# PWMExpansion.net
KiCad netlist of a schematic drawn in EAGLE
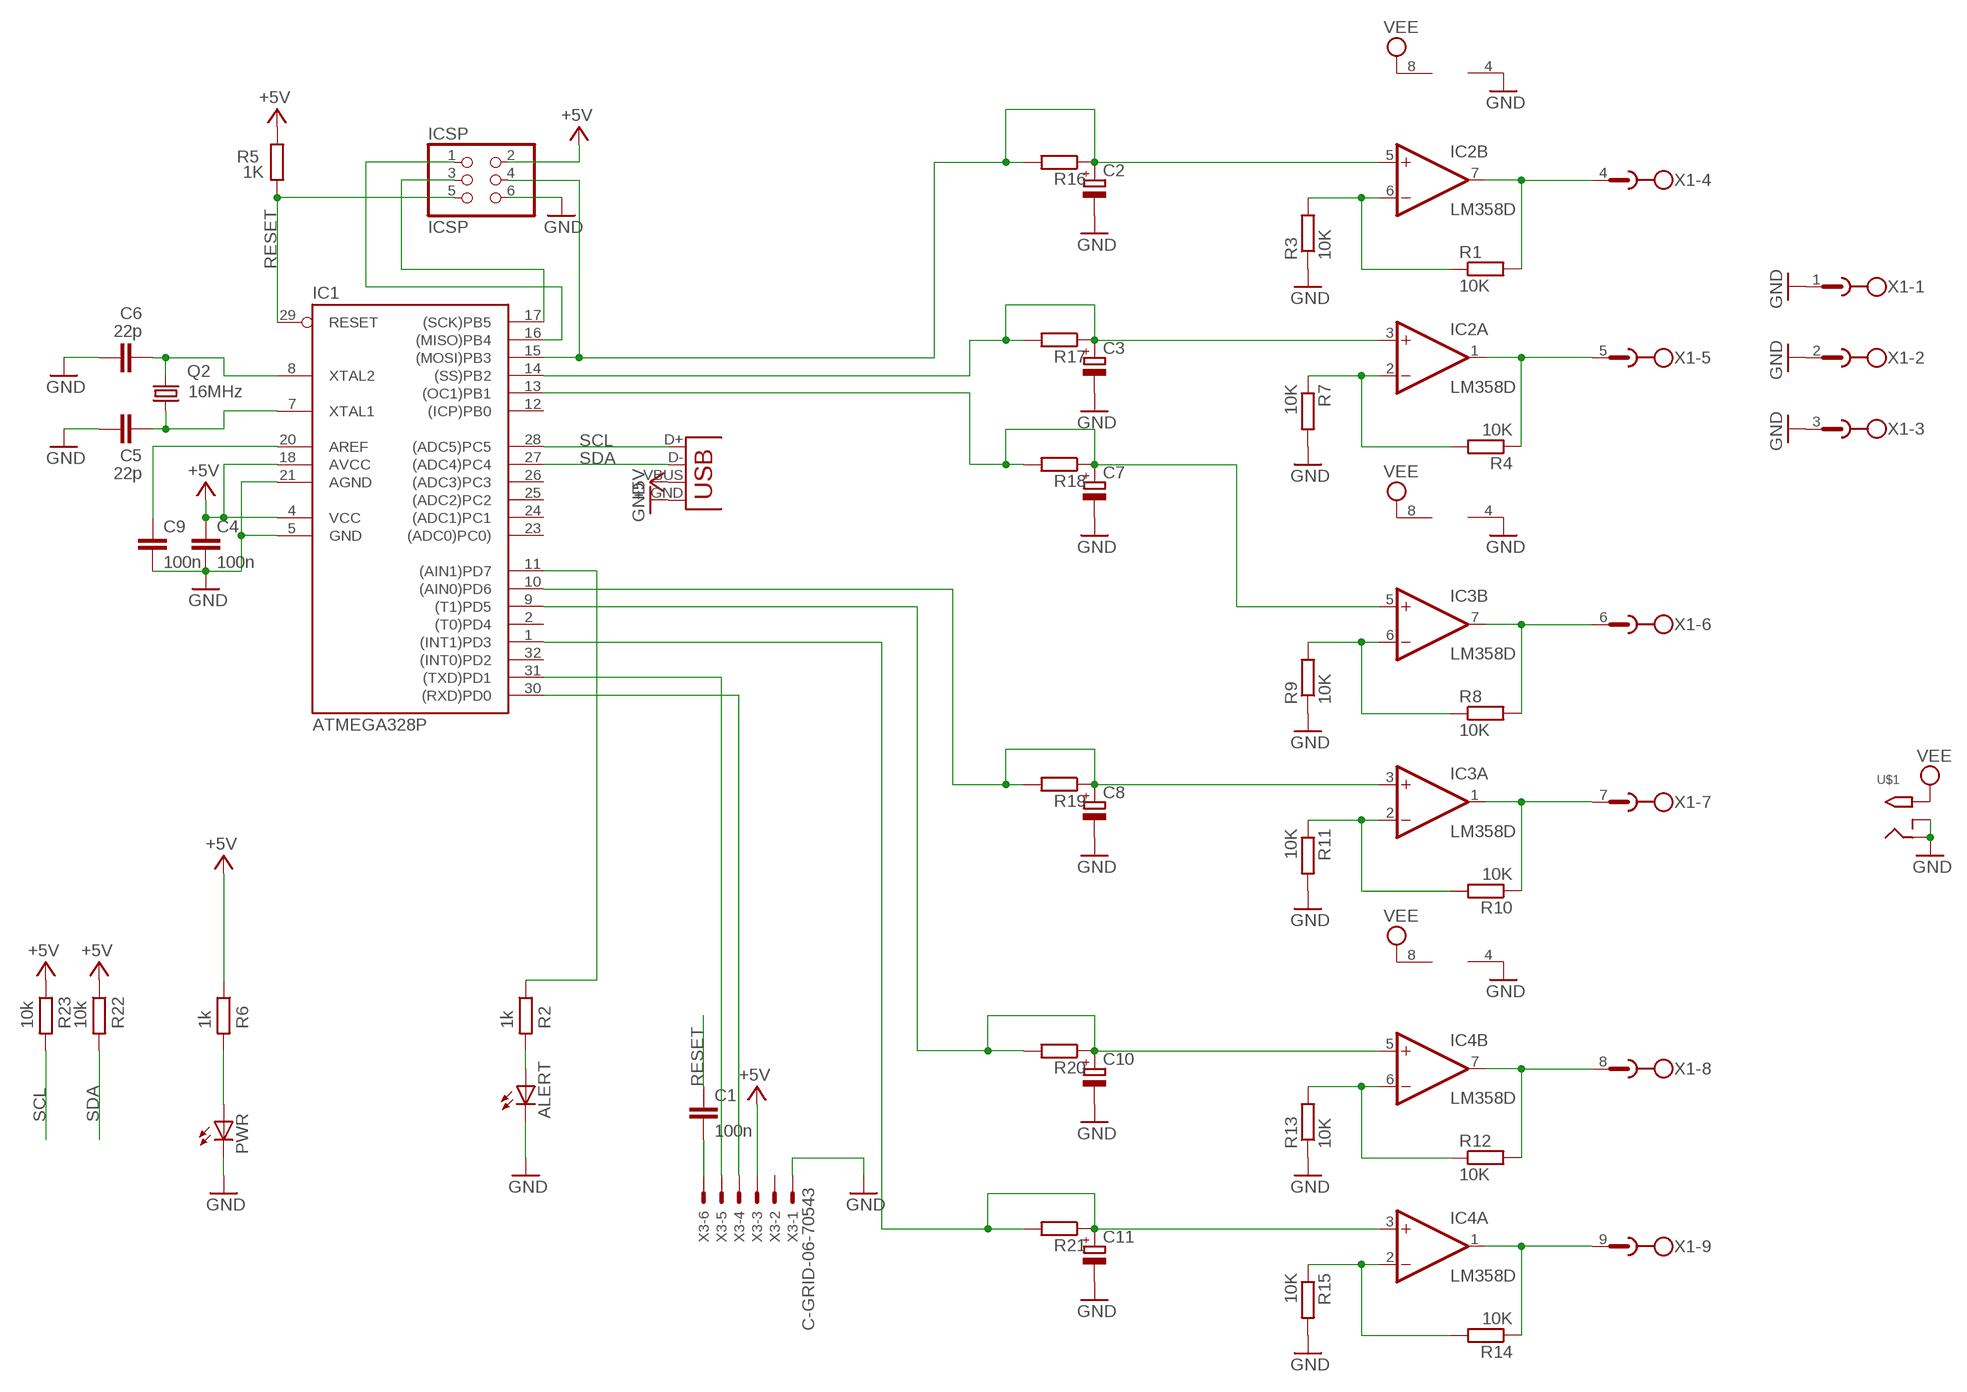
[diagram p0: schematic, sheet 1]

(export (version "E")
  (design (tool "Eeschema 10.0.6"))
  (components
    (comp (ref "ALERT")
      (value "LED3MM")
      (footprint "eagle-import:LED3MM")
      (libsource (lib "eagle-import") (part "LED3MM"))
    )
    (comp (ref "C1")
      (value "100n")
      (footprint "eagle-import:C0805")
      (libsource (lib "eagle-import") (part "C-EUC0805"))
    )
    (comp (ref "C2")
      (value "CPOL-EUA/3216-18W")
      (footprint "eagle-import:A_3216-18W")
      (libsource (lib "eagle-import") (part "CPOL-EUA/3216-18W"))
    )
    (comp (ref "C3")
      (value "CPOL-EUA/3216-18W")
      (footprint "eagle-import:A_3216-18W")
      (libsource (lib "eagle-import") (part "CPOL-EUA/3216-18W"))
    )
    (comp (ref "C4")
      (value "100n")
      (footprint "eagle-import:C0805")
      (libsource (lib "eagle-import") (part "C-EUC0805"))
    )
    (comp (ref "C5")
      (value "22p")
      (footprint "eagle-import:C0805")
      (libsource (lib "eagle-import") (part "C-EUC0805"))
    )
    (comp (ref "C6")
      (value "22p")
      (footprint "eagle-import:C0805")
      (libsource (lib "eagle-import") (part "C-EUC0805"))
    )
    (comp (ref "C7")
      (value "CPOL-EUA/3216-18W")
      (footprint "eagle-import:A_3216-18W")
      (libsource (lib "eagle-import") (part "CPOL-EUA/3216-18W"))
    )
    (comp (ref "C8")
      (value "CPOL-EUA/3216-18W")
      (footprint "eagle-import:A_3216-18W")
      (libsource (lib "eagle-import") (part "CPOL-EUA/3216-18W"))
    )
    (comp (ref "C9")
      (value "100n")
      (footprint "eagle-import:C0805")
      (libsource (lib "eagle-import") (part "C-EUC0805"))
    )
    (comp (ref "C10")
      (value "CPOL-EUA/3216-18W")
      (footprint "eagle-import:A_3216-18W")
      (libsource (lib "eagle-import") (part "CPOL-EUA/3216-18W"))
    )
    (comp (ref "C11")
      (value "CPOL-EUA/3216-18W")
      (footprint "eagle-import:A_3216-18W")
      (libsource (lib "eagle-import") (part "CPOL-EUA/3216-18W"))
    )
    (comp (ref "IC1")
      (value "ATMEGA328P")
      (footprint "eagle-import:TQFP32-08")
      (libsource (lib "eagle-import") (part "AT90S4433A"))
    )
    (comp (ref "IC2")
      (value "LM358D")
      (footprint "eagle-import:SO08")
      (libsource (lib "eagle-import") (part "LM358D"))
    )
    (comp (ref "IC3")
      (value "LM358D")
      (footprint "eagle-import:SO08")
      (libsource (lib "eagle-import") (part "LM358D"))
    )
    (comp (ref "IC4")
      (value "LM358D")
      (footprint "eagle-import:SO08")
      (libsource (lib "eagle-import") (part "LM358D"))
    )
    (comp (ref "ICSP")
      (value "ICSP")
      (footprint "eagle-import:2X03")
      (libsource (lib "eagle-import") (part "PINHD-2X3"))
    )
    (comp (ref "PWR")
      (value "LED3MM")
      (footprint "eagle-import:LED3MM")
      (libsource (lib "eagle-import") (part "LED3MM"))
    )
    (comp (ref "Q2")
      (value "16MHz")
      (footprint "eagle-import:HC49_S")
      (libsource (lib "eagle-import") (part "CRYTALHC49S"))
    )
    (comp (ref "R1")
      (value "10K")
      (footprint "eagle-import:R0805")
      (libsource (lib "eagle-import") (part "R-EU_R0805"))
    )
    (comp (ref "R2")
      (value "1k")
      (footprint "eagle-import:R0805")
      (libsource (lib "eagle-import") (part "R-EU_R0805"))
    )
    (comp (ref "R3")
      (value "10K")
      (footprint "eagle-import:R0805")
      (libsource (lib "eagle-import") (part "R-EU_R0805"))
    )
    (comp (ref "R4")
      (value "10K")
      (footprint "eagle-import:R0805")
      (libsource (lib "eagle-import") (part "R-EU_R0805"))
    )
    (comp (ref "R5")
      (value "1K")
      (footprint "eagle-import:R0805")
      (libsource (lib "eagle-import") (part "R-EU_R0805"))
    )
    (comp (ref "R6")
      (value "1k")
      (footprint "eagle-import:R0805")
      (libsource (lib "eagle-import") (part "R-EU_R0805"))
    )
    (comp (ref "R7")
      (value "10K")
      (footprint "eagle-import:R0805")
      (libsource (lib "eagle-import") (part "R-EU_R0805"))
    )
    (comp (ref "R8")
      (value "10K")
      (footprint "eagle-import:R0805")
      (libsource (lib "eagle-import") (part "R-EU_R0805"))
    )
    (comp (ref "R9")
      (value "10K")
      (footprint "eagle-import:R0805")
      (libsource (lib "eagle-import") (part "R-EU_R0805"))
    )
    (comp (ref "R10")
      (value "10K")
      (footprint "eagle-import:R0805")
      (libsource (lib "eagle-import") (part "R-EU_R0805"))
    )
    (comp (ref "R11")
      (value "10K")
      (footprint "eagle-import:R0805")
      (libsource (lib "eagle-import") (part "R-EU_R0805"))
    )
    (comp (ref "R12")
      (value "10K")
      (footprint "eagle-import:R0805")
      (libsource (lib "eagle-import") (part "R-EU_R0805"))
    )
    (comp (ref "R13")
      (value "10K")
      (footprint "eagle-import:R0805")
      (libsource (lib "eagle-import") (part "R-EU_R0805"))
    )
    (comp (ref "R14")
      (value "10K")
      (footprint "eagle-import:R0805")
      (libsource (lib "eagle-import") (part "R-EU_R0805"))
    )
    (comp (ref "R15")
      (value "10K")
      (footprint "eagle-import:R0805")
      (libsource (lib "eagle-import") (part "R-EU_R0805"))
    )
    (comp (ref "R16")
      (value "R-EU_R0805")
      (footprint "eagle-import:R0805")
      (libsource (lib "eagle-import") (part "R-EU_R0805"))
    )
    (comp (ref "R17")
      (value "R-EU_R0805")
      (footprint "eagle-import:R0805")
      (libsource (lib "eagle-import") (part "R-EU_R0805"))
    )
    (comp (ref "R18")
      (value "R-EU_R0805")
      (footprint "eagle-import:R0805")
      (libsource (lib "eagle-import") (part "R-EU_R0805"))
    )
    (comp (ref "R19")
      (value "R-EU_R0805")
      (footprint "eagle-import:R0805")
      (libsource (lib "eagle-import") (part "R-EU_R0805"))
    )
    (comp (ref "R20")
      (value "R-EU_R0805")
      (footprint "eagle-import:R0805")
      (libsource (lib "eagle-import") (part "R-EU_R0805"))
    )
    (comp (ref "R21")
      (value "R-EU_R0805")
      (footprint "eagle-import:R0805")
      (libsource (lib "eagle-import") (part "R-EU_R0805"))
    )
    (comp (ref "R22")
      (value "10k")
      (footprint "eagle-import:R0805")
      (libsource (lib "eagle-import") (part "R-EU_R0805"))
    )
    (comp (ref "R23")
      (value "10k")
      (footprint "eagle-import:R0805")
      (libsource (lib "eagle-import") (part "R-EU_R0805"))
    )
    (comp (ref "U$1")
      (value "2.1MMJACKTHM")
      (footprint "eagle-import:PJ-102A")
      (libsource (lib "eagle-import") (part "2.1MMJACKTHM"))
    )
    (comp (ref "X1")
      (value "MSTBV9")
      (footprint "eagle-import:MSTBV9")
      (libsource (lib "eagle-import") (part "MSTBV9"))
    )
    (comp (ref "X3")
      (value "C-GRID-06-70543")
      (footprint "eagle-import:70543-06")
      (libsource (lib "eagle-import") (part "C-GRID-06-70543"))
    )
    (comp (ref "X5")
      (value "USBSMD")
      (footprint "eagle-import:USB-MINIB")
      (libsource (lib "eagle-import") (part "USBSMD"))
    )
  )
  (nets
    (net (code "1") (name "+5V") (class "Default")
      (node (ref "C4") (pin "1") (pinfunction "1_1") (pintype "passive"))
      (node (ref "IC1") (pin "18") (pinfunction "AVCC_18") (pintype "power_in"))
      (node (ref "IC1") (pin "4") (pinfunction "VCC_4") (pintype "power_in"))
      (node (ref "ICSP") (pin "2") (pinfunction "2_2") (pintype "passive"))
      (node (ref "R22") (pin "1") (pinfunction "1_1") (pintype "passive"))
      (node (ref "R23") (pin "1") (pinfunction "1_1") (pintype "passive"))
      (node (ref "R5") (pin "2") (pinfunction "2_2") (pintype "passive"))
      (node (ref "R6") (pin "1") (pinfunction "1_1") (pintype "passive"))
      (node (ref "X3") (pin "3") (pinfunction "S_3") (pintype "passive"))
      (node (ref "X5") (pin "VBUS") (pinfunction "VBUS_VBUS") (pintype "bidirectional"))
    )
    (net (code "2") (name "/RESET") (class "Default")
      (node (ref "C1") (pin "1") (pinfunction "1_1") (pintype "passive"))
      (node (ref "IC1") (pin "29") (pinfunction "RESET_29") (pintype "input"))
      (node (ref "ICSP") (pin "5") (pinfunction "5_5") (pintype "passive"))
      (node (ref "R5") (pin "1") (pinfunction "1_1") (pintype "passive"))
    )
    (net (code "3") (name "/SCL") (class "Default")
      (node (ref "IC1") (pin "28") (pinfunction "(ADC5)PC5_28") (pintype "bidirectional"))
      (node (ref "R23") (pin "2") (pinfunction "2_2") (pintype "passive"))
      (node (ref "X5") (pin "D+") (pinfunction "D+_D+") (pintype "bidirectional"))
    )
    (net (code "4") (name "/SDA") (class "Default")
      (node (ref "IC1") (pin "27") (pinfunction "(ADC4)PC4_27") (pintype "bidirectional"))
      (node (ref "R22") (pin "2") (pinfunction "2_2") (pintype "passive"))
      (node (ref "X5") (pin "D-") (pinfunction "D-_D-") (pintype "bidirectional"))
    )
    (net (code "5") (name "GND") (class "Default")
      (node (ref "ALERT") (pin "K") (pinfunction "C_K") (pintype "passive"))
      (node (ref "C10") (pin "-") (pinfunction "-_-") (pintype "passive"))
      (node (ref "C11") (pin "-") (pinfunction "-_-") (pintype "passive"))
      (node (ref "C2") (pin "-") (pinfunction "-_-") (pintype "passive"))
      (node (ref "C3") (pin "-") (pinfunction "-_-") (pintype "passive"))
      (node (ref "C4") (pin "2") (pinfunction "2_2") (pintype "passive"))
      (node (ref "C5") (pin "1") (pinfunction "1_1") (pintype "passive"))
      (node (ref "C6") (pin "1") (pinfunction "1_1") (pintype "passive"))
      (node (ref "C7") (pin "-") (pinfunction "-_-") (pintype "passive"))
      (node (ref "C8") (pin "-") (pinfunction "-_-") (pintype "passive"))
      (node (ref "C9") (pin "2") (pinfunction "2_2") (pintype "passive"))
      (node (ref "IC1") (pin "21") (pinfunction "AGND_21") (pintype "power_in"))
      (node (ref "IC1") (pin "5") (pinfunction "GND_5") (pintype "power_in"))
      (node (ref "IC2") (pin "4") (pinfunction "V-_4") (pintype "power_in"))
      (node (ref "IC3") (pin "4") (pinfunction "V-_4") (pintype "power_in"))
      (node (ref "IC4") (pin "4") (pinfunction "V-_4") (pintype "power_in"))
      (node (ref "ICSP") (pin "6") (pinfunction "6_6") (pintype "passive"))
      (node (ref "PWR") (pin "K") (pinfunction "C_K") (pintype "passive"))
      (node (ref "R11") (pin "2") (pinfunction "2_2") (pintype "passive"))
      (node (ref "R13") (pin "1") (pinfunction "1_1") (pintype "passive"))
      (node (ref "R15") (pin "2") (pinfunction "2_2") (pintype "passive"))
      (node (ref "R3") (pin "1") (pinfunction "1_1") (pintype "passive"))
      (node (ref "R7") (pin "2") (pinfunction "2_2") (pintype "passive"))
      (node (ref "R9") (pin "1") (pinfunction "1_1") (pintype "passive"))
      (node (ref "U$1") (pin "RING") (pinfunction "RING_RING") (pintype "bidirectional"))
      (node (ref "U$1") (pin "RING_SW") (pinfunction "RING_SW_RING_SW") (pintype "bidirectional"))
      (node (ref "X1") (pin "1") (pinfunction "1_1") (pintype "passive"))
      (node (ref "X1") (pin "2") (pinfunction "1_2") (pintype "passive"))
      (node (ref "X1") (pin "3") (pinfunction "1_3") (pintype "passive"))
      (node (ref "X3") (pin "1") (pinfunction "S_1") (pintype "passive"))
      (node (ref "X5") (pin "GND") (pinfunction "GND_GND") (pintype "bidirectional"))
    )
    (net (code "6") (name "Net-(ALERT-PadA)") (class "Default")
      (node (ref "ALERT") (pin "A") (pinfunction "A_A") (pintype "passive"))
      (node (ref "R2") (pin "2") (pinfunction "2_2") (pintype "passive"))
    )
    (net (code "7") (name "Net-(IC1-(AIN0)PD6)") (class "Default")
      (node (ref "C8") (pin "+") (pinfunction "+_+") (pintype "passive"))
      (node (ref "IC1") (pin "10") (pinfunction "(AIN0)PD6_10") (pintype "bidirectional"))
      (node (ref "IC3") (pin "3") (pinfunction "+IN_3") (pintype "input"))
      (node (ref "R19") (pin "1") (pinfunction "1_1") (pintype "passive"))
      (node (ref "R19") (pin "2") (pinfunction "2_2") (pintype "passive"))
    )
    (net (code "8") (name "Net-(IC1-(AIN1)PD7)") (class "Default")
      (node (ref "IC1") (pin "11") (pinfunction "(AIN1)PD7_11") (pintype "bidirectional"))
      (node (ref "R2") (pin "1") (pinfunction "1_1") (pintype "passive"))
    )
    (net (code "9") (name "Net-(IC1-(INT1)PD3)") (class "Default")
      (node (ref "C11") (pin "+") (pinfunction "+_+") (pintype "passive"))
      (node (ref "IC1") (pin "1") (pinfunction "(INT1)PD3_1") (pintype "bidirectional"))
      (node (ref "IC4") (pin "3") (pinfunction "+IN_3") (pintype "input"))
      (node (ref "R21") (pin "1") (pinfunction "1_1") (pintype "passive"))
      (node (ref "R21") (pin "2") (pinfunction "2_2") (pintype "passive"))
    )
    (net (code "10") (name "Net-(IC1-(MISO)PB4)") (class "Default")
      (node (ref "IC1") (pin "16") (pinfunction "(MISO)PB4_16") (pintype "bidirectional"))
      (node (ref "ICSP") (pin "1") (pinfunction "1_1") (pintype "passive"))
    )
    (net (code "11") (name "Net-(IC1-(MOSI)PB3)") (class "Default")
      (node (ref "C2") (pin "+") (pinfunction "+_+") (pintype "passive"))
      (node (ref "IC1") (pin "15") (pinfunction "(MOSI)PB3_15") (pintype "bidirectional"))
      (node (ref "IC2") (pin "5") (pinfunction "+IN_5") (pintype "input"))
      (node (ref "ICSP") (pin "4") (pinfunction "4_4") (pintype "passive"))
      (node (ref "R16") (pin "1") (pinfunction "1_1") (pintype "passive"))
      (node (ref "R16") (pin "2") (pinfunction "2_2") (pintype "passive"))
    )
    (net (code "12") (name "Net-(IC1-(OC1)PB1)") (class "Default")
      (node (ref "C7") (pin "+") (pinfunction "+_+") (pintype "passive"))
      (node (ref "IC1") (pin "13") (pinfunction "(OC1)PB1_13") (pintype "bidirectional"))
      (node (ref "IC3") (pin "5") (pinfunction "+IN_5") (pintype "input"))
      (node (ref "R18") (pin "1") (pinfunction "1_1") (pintype "passive"))
      (node (ref "R18") (pin "2") (pinfunction "2_2") (pintype "passive"))
    )
    (net (code "13") (name "Net-(IC1-(RXD)PD0)") (class "Default")
      (node (ref "IC1") (pin "30") (pinfunction "(RXD)PD0_30") (pintype "bidirectional"))
      (node (ref "X3") (pin "4") (pinfunction "S_4") (pintype "passive"))
    )
    (net (code "14") (name "Net-(IC1-(SCK)PB5)") (class "Default")
      (node (ref "IC1") (pin "17") (pinfunction "(SCK)PB5_17") (pintype "bidirectional"))
      (node (ref "ICSP") (pin "3") (pinfunction "3_3") (pintype "passive"))
    )
    (net (code "15") (name "Net-(IC1-(SS)PB2)") (class "Default")
      (node (ref "C3") (pin "+") (pinfunction "+_+") (pintype "passive"))
      (node (ref "IC1") (pin "14") (pinfunction "(SS)PB2_14") (pintype "bidirectional"))
      (node (ref "IC2") (pin "3") (pinfunction "+IN_3") (pintype "input"))
      (node (ref "R17") (pin "1") (pinfunction "1_1") (pintype "passive"))
      (node (ref "R17") (pin "2") (pinfunction "2_2") (pintype "passive"))
    )
    (net (code "16") (name "Net-(IC1-(T1)PD5)") (class "Default")
      (node (ref "C10") (pin "+") (pinfunction "+_+") (pintype "passive"))
      (node (ref "IC1") (pin "9") (pinfunction "(T1)PD5_9") (pintype "bidirectional"))
      (node (ref "IC4") (pin "5") (pinfunction "+IN_5") (pintype "input"))
      (node (ref "R20") (pin "1") (pinfunction "1_1") (pintype "passive"))
      (node (ref "R20") (pin "2") (pinfunction "2_2") (pintype "passive"))
    )
    (net (code "17") (name "Net-(IC1-(TXD)PD1)") (class "Default")
      (node (ref "IC1") (pin "31") (pinfunction "(TXD)PD1_31") (pintype "bidirectional"))
      (node (ref "X3") (pin "5") (pinfunction "S_5") (pintype "passive"))
    )
    (net (code "18") (name "Net-(IC1-AREF)") (class "Default")
      (node (ref "C9") (pin "1") (pinfunction "1_1") (pintype "passive"))
      (node (ref "IC1") (pin "20") (pinfunction "AREF_20") (pintype "passive"))
    )
    (net (code "19") (name "Net-(IC1-XTAL1)") (class "Default")
      (node (ref "C5") (pin "2") (pinfunction "2_2") (pintype "passive"))
      (node (ref "IC1") (pin "7") (pinfunction "XTAL1_7") (pintype "bidirectional"))
      (node (ref "Q2") (pin "1") (pinfunction "1_1") (pintype "passive"))
    )
    (net (code "20") (name "Net-(IC1-XTAL2)") (class "Default")
      (node (ref "C6") (pin "2") (pinfunction "2_2") (pintype "passive"))
      (node (ref "IC1") (pin "8") (pinfunction "XTAL2_8") (pintype "bidirectional"))
      (node (ref "Q2") (pin "2") (pinfunction "2_2") (pintype "passive"))
    )
    (net (code "21") (name "Net-(IC2A--IN)") (class "Default")
      (node (ref "IC2") (pin "2") (pinfunction "-IN_2") (pintype "input"))
      (node (ref "R4") (pin "2") (pinfunction "2_2") (pintype "passive"))
      (node (ref "R7") (pin "1") (pinfunction "1_1") (pintype "passive"))
    )
    (net (code "22") (name "Net-(IC2A-OUT)") (class "Default")
      (node (ref "IC2") (pin "1") (pinfunction "OUT_1") (pintype "output"))
      (node (ref "R4") (pin "1") (pinfunction "1_1") (pintype "passive"))
      (node (ref "X1") (pin "5") (pinfunction "1_5") (pintype "passive"))
    )
    (net (code "23") (name "Net-(IC2B--IN)") (class "Default")
      (node (ref "IC2") (pin "6") (pinfunction "-IN_6") (pintype "input"))
      (node (ref "R1") (pin "1") (pinfunction "1_1") (pintype "passive"))
      (node (ref "R3") (pin "2") (pinfunction "2_2") (pintype "passive"))
    )
    (net (code "24") (name "Net-(IC2B-OUT)") (class "Default")
      (node (ref "IC2") (pin "7") (pinfunction "OUT_7") (pintype "output"))
      (node (ref "R1") (pin "2") (pinfunction "2_2") (pintype "passive"))
      (node (ref "X1") (pin "4") (pinfunction "1_4") (pintype "passive"))
    )
    (net (code "25") (name "Net-(IC3A--IN)") (class "Default")
      (node (ref "IC3") (pin "2") (pinfunction "-IN_2") (pintype "input"))
      (node (ref "R10") (pin "2") (pinfunction "2_2") (pintype "passive"))
      (node (ref "R11") (pin "1") (pinfunction "1_1") (pintype "passive"))
    )
    (net (code "26") (name "Net-(IC3A-OUT)") (class "Default")
      (node (ref "IC3") (pin "1") (pinfunction "OUT_1") (pintype "output"))
      (node (ref "R10") (pin "1") (pinfunction "1_1") (pintype "passive"))
      (node (ref "X1") (pin "7") (pinfunction "1_7") (pintype "passive"))
    )
    (net (code "27") (name "Net-(IC3B--IN)") (class "Default")
      (node (ref "IC3") (pin "6") (pinfunction "-IN_6") (pintype "input"))
      (node (ref "R8") (pin "1") (pinfunction "1_1") (pintype "passive"))
      (node (ref "R9") (pin "2") (pinfunction "2_2") (pintype "passive"))
    )
    (net (code "28") (name "Net-(IC3B-OUT)") (class "Default")
      (node (ref "IC3") (pin "7") (pinfunction "OUT_7") (pintype "output"))
      (node (ref "R8") (pin "2") (pinfunction "2_2") (pintype "passive"))
      (node (ref "X1") (pin "6") (pinfunction "1_6") (pintype "passive"))
    )
    (net (code "29") (name "Net-(IC4A--IN)") (class "Default")
      (node (ref "IC4") (pin "2") (pinfunction "-IN_2") (pintype "input"))
      (node (ref "R14") (pin "2") (pinfunction "2_2") (pintype "passive"))
      (node (ref "R15") (pin "1") (pinfunction "1_1") (pintype "passive"))
    )
    (net (code "30") (name "Net-(IC4A-OUT)") (class "Default")
      (node (ref "IC4") (pin "1") (pinfunction "OUT_1") (pintype "output"))
      (node (ref "R14") (pin "1") (pinfunction "1_1") (pintype "passive"))
      (node (ref "X1") (pin "9") (pinfunction "1_9") (pintype "passive"))
    )
    (net (code "31") (name "Net-(IC4B--IN)") (class "Default")
      (node (ref "IC4") (pin "6") (pinfunction "-IN_6") (pintype "input"))
      (node (ref "R12") (pin "1") (pinfunction "1_1") (pintype "passive"))
      (node (ref "R13") (pin "2") (pinfunction "2_2") (pintype "passive"))
    )
    (net (code "32") (name "Net-(IC4B-OUT)") (class "Default")
      (node (ref "IC4") (pin "7") (pinfunction "OUT_7") (pintype "output"))
      (node (ref "R12") (pin "2") (pinfunction "2_2") (pintype "passive"))
      (node (ref "X1") (pin "8") (pinfunction "1_8") (pintype "passive"))
    )
    (net (code "33") (name "Net-(PWR-PadA)") (class "Default")
      (node (ref "PWR") (pin "A") (pinfunction "A_A") (pintype "passive"))
      (node (ref "R6") (pin "2") (pinfunction "2_2") (pintype "passive"))
    )
    (net (code "34") (name "Net-(X3F-S)") (class "Default")
      (node (ref "C1") (pin "2") (pinfunction "2_2") (pintype "passive"))
      (node (ref "X3") (pin "6") (pinfunction "S_6") (pintype "passive"))
    )
    (net (code "35") (name "VEE") (class "Default")
      (node (ref "IC2") (pin "8") (pinfunction "V+_8") (pintype "power_in"))
      (node (ref "IC3") (pin "8") (pinfunction "V+_8") (pintype "power_in"))
      (node (ref "IC4") (pin "8") (pinfunction "V+_8") (pintype "power_in"))
      (node (ref "U$1") (pin "TIP") (pinfunction "TIP_TIP") (pintype "bidirectional"))
    )
    (net (code "36") (name "unconnected-(IC1-(ADC0)PC0)-Pad23)") (class "Default")
      (node (ref "IC1") (pin "23") (pinfunction "(ADC0)PC0)_23") (pintype "bidirectional"))
    )
    (net (code "37") (name "unconnected-(IC1-(ADC1)PC1-Pad24)") (class "Default")
      (node (ref "IC1") (pin "24") (pinfunction "(ADC1)PC1_24") (pintype "bidirectional"))
    )
    (net (code "38") (name "unconnected-(IC1-(ADC2)PC2-Pad25)") (class "Default")
      (node (ref "IC1") (pin "25") (pinfunction "(ADC2)PC2_25") (pintype "bidirectional"))
    )
    (net (code "39") (name "unconnected-(IC1-(ADC3)PC3-Pad26)") (class "Default")
      (node (ref "IC1") (pin "26") (pinfunction "(ADC3)PC3_26") (pintype "bidirectional"))
    )
    (net (code "40") (name "unconnected-(IC1-(ICP)PB0-Pad12)") (class "Default")
      (node (ref "IC1") (pin "12") (pinfunction "(ICP)PB0_12") (pintype "bidirectional"))
    )
    (net (code "41") (name "unconnected-(IC1-(INT0)PD2-Pad32)") (class "Default")
      (node (ref "IC1") (pin "32") (pinfunction "(INT0)PD2_32") (pintype "bidirectional"))
    )
    (net (code "42") (name "unconnected-(IC1-(T0)PD4-Pad2)") (class "Default")
      (node (ref "IC1") (pin "2") (pinfunction "(T0)PD4_2") (pintype "bidirectional"))
    )
    (net (code "43") (name "unconnected-(X3B-S-Pad2)") (class "Default")
      (node (ref "X3") (pin "2") (pinfunction "S_2") (pintype "passive"))
    )
  )
)
